# Interconnect_board_v1p9.net
KiCad netlist of a schematic drawn in EAGLE
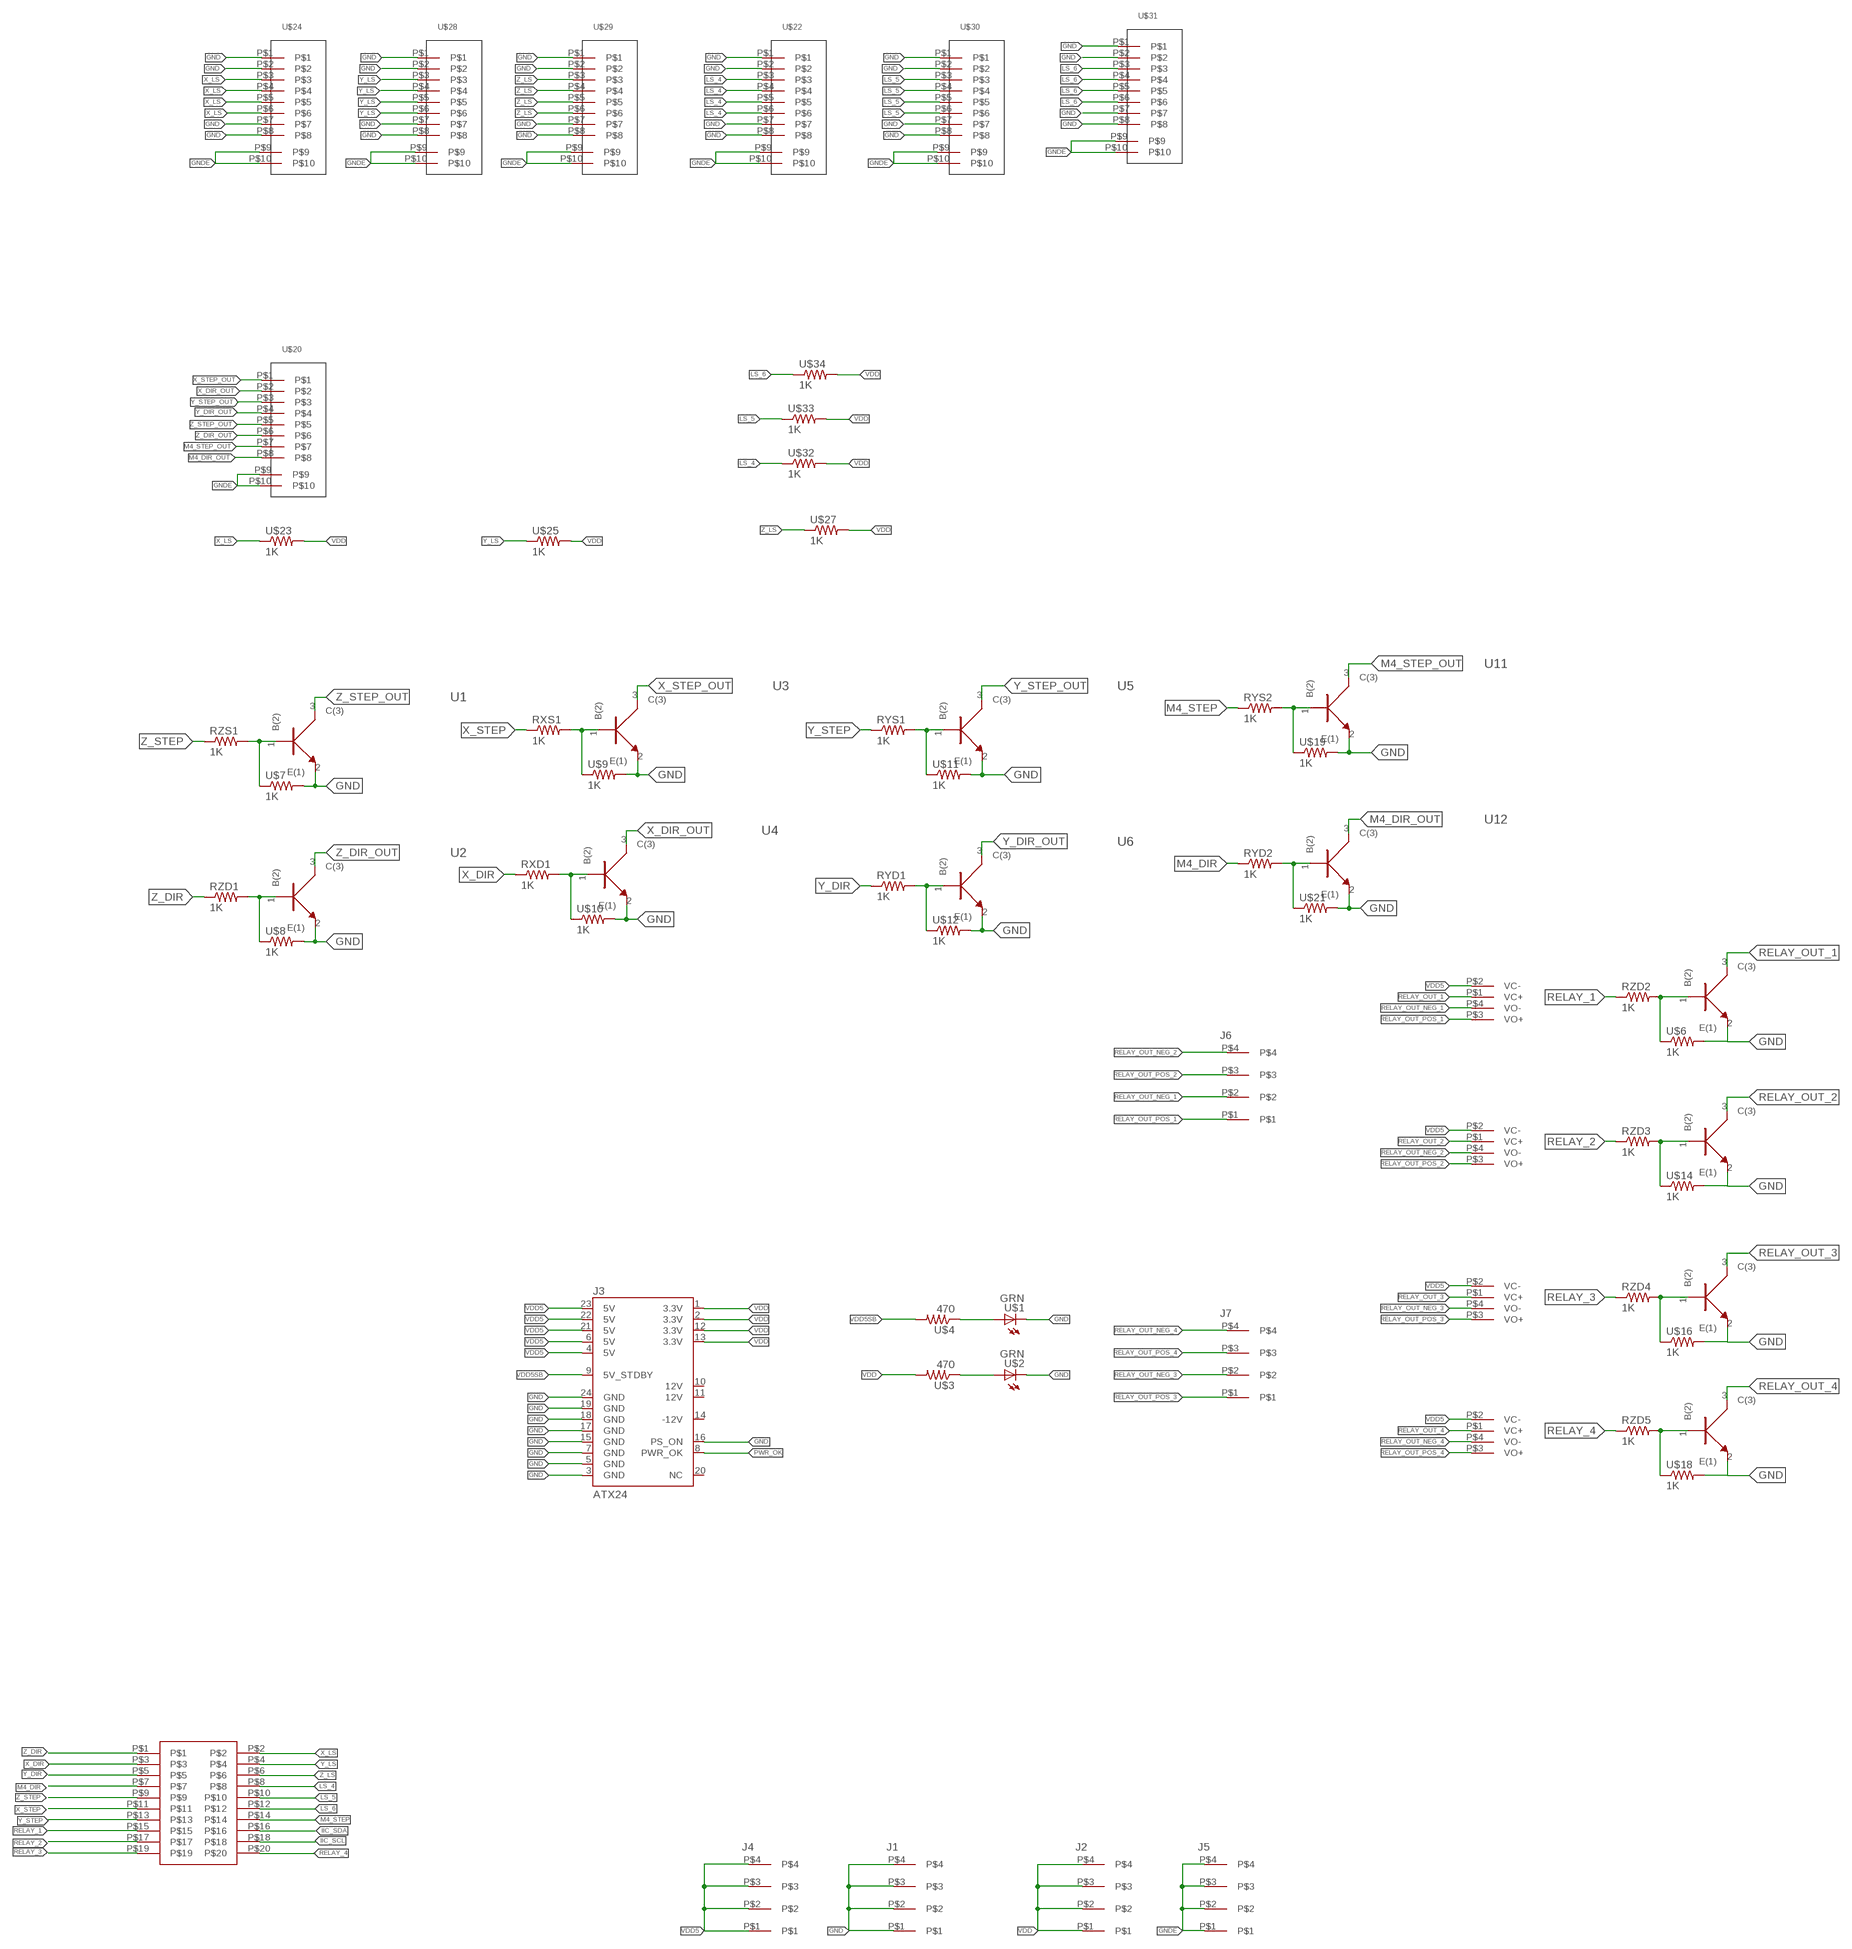
[diagram p0: schematic, sheet 1]

(export (version "E")
  (design (tool "Eeschema 10.0.6"))
  (components
    (comp (ref "J1")
      (value "3.81MM_1_X_4_RT_ANGLE_PLUG_HEADER")
      (footprint "eagle-import:1X4_3.81MM_PITCH")
      (libsource (lib "eagle-import") (part "3.81MM_1_X_4_RT_ANGLE_PLUG_HEADER"))
    )
    (comp (ref "J2")
      (value "3.81MM_1_X_4_RT_ANGLE_PLUG_HEADER")
      (footprint "eagle-import:1X4_3.81MM_PITCH")
      (libsource (lib "eagle-import") (part "3.81MM_1_X_4_RT_ANGLE_PLUG_HEADER"))
    )
    (comp (ref "J3")
      (value "ATX24")
      (footprint "eagle-import:ATX24_STRAIGHT")
      (libsource (lib "eagle-import") (part "ATX24"))
    )
    (comp (ref "J4")
      (value "3.81MM_1_X_4_RT_ANGLE_PLUG_HEADER")
      (footprint "eagle-import:1X4_3.81MM_PITCH")
      (libsource (lib "eagle-import") (part "3.81MM_1_X_4_RT_ANGLE_PLUG_HEADER"))
    )
    (comp (ref "J5")
      (value "3.81MM_1_X_4_RT_ANGLE_PLUG_HEADER")
      (footprint "eagle-import:1X4_3.81MM_PITCH")
      (libsource (lib "eagle-import") (part "3.81MM_1_X_4_RT_ANGLE_PLUG_HEADER"))
    )
    (comp (ref "J6")
      (value "3.81MM_1_X_4_RT_ANGLE_PLUG_HEADER")
      (footprint "eagle-import:1X4_3.81MM_PITCH")
      (libsource (lib "eagle-import") (part "3.81MM_1_X_4_RT_ANGLE_PLUG_HEADER"))
    )
    (comp (ref "J7")
      (value "3.81MM_1_X_4_RT_ANGLE_PLUG_HEADER")
      (footprint "eagle-import:1X4_3.81MM_PITCH")
      (libsource (lib "eagle-import") (part "3.81MM_1_X_4_RT_ANGLE_PLUG_HEADER"))
    )
    (comp (ref "RXD1")
      (value "R_0805_1K")
      (footprint "eagle-import:R_0805_1K")
      (libsource (lib "eagle-import") (part "R_0805_1K"))
    )
    (comp (ref "RXS1")
      (value "R_0805_1K")
      (footprint "eagle-import:R_0805_1K")
      (libsource (lib "eagle-import") (part "R_0805_1K"))
    )
    (comp (ref "RYD1")
      (value "R_0805_1K")
      (footprint "eagle-import:R_0805_1K")
      (libsource (lib "eagle-import") (part "R_0805_1K"))
    )
    (comp (ref "RYD2")
      (value "R_0805_1K")
      (footprint "eagle-import:R_0805_1K")
      (libsource (lib "eagle-import") (part "R_0805_1K"))
    )
    (comp (ref "RYS1")
      (value "R_0805_1K")
      (footprint "eagle-import:R_0805_1K")
      (libsource (lib "eagle-import") (part "R_0805_1K"))
    )
    (comp (ref "RYS2")
      (value "R_0805_1K")
      (footprint "eagle-import:R_0805_1K")
      (libsource (lib "eagle-import") (part "R_0805_1K"))
    )
    (comp (ref "RZD1")
      (value "R_0805_1K")
      (footprint "eagle-import:R_0805_1K")
      (libsource (lib "eagle-import") (part "R_0805_1K"))
    )
    (comp (ref "RZD2")
      (value "R_0805_1K")
      (footprint "eagle-import:R_0805_1K")
      (libsource (lib "eagle-import") (part "R_0805_1K"))
    )
    (comp (ref "RZD3")
      (value "R_0805_1K")
      (footprint "eagle-import:R_0805_1K")
      (libsource (lib "eagle-import") (part "R_0805_1K"))
    )
    (comp (ref "RZD4")
      (value "R_0805_1K")
      (footprint "eagle-import:R_0805_1K")
      (libsource (lib "eagle-import") (part "R_0805_1K"))
    )
    (comp (ref "RZD5")
      (value "R_0805_1K")
      (footprint "eagle-import:R_0805_1K")
      (libsource (lib "eagle-import") (part "R_0805_1K"))
    )
    (comp (ref "RZS1")
      (value "R_0805_1K")
      (footprint "eagle-import:R_0805_1K")
      (libsource (lib "eagle-import") (part "R_0805_1K"))
    )
    (comp (ref "U$1")
      (value "LED_0805_GREEN")
      (footprint "eagle-import:LED_0805_GREEN")
      (libsource (lib "eagle-import") (part "LED_0805_GREEN"))
    )
    (comp (ref "U$2")
      (value "LED_0805_GREEN")
      (footprint "eagle-import:LED_0805_GREEN")
      (libsource (lib "eagle-import") (part "LED_0805_GREEN"))
    )
    (comp (ref "U$3")
      (value "R_0805_470")
      (footprint "eagle-import:R_0805_470")
      (libsource (lib "eagle-import") (part "R_0805_470"))
    )
    (comp (ref "U$4")
      (value "R_0805_470")
      (footprint "eagle-import:R_0805_470")
      (libsource (lib "eagle-import") (part "R_0805_470"))
    )
    (comp (ref "U$5")
      (value "RELAY_KYOTO_KF0604D")
      (footprint "eagle-import:RELAY_KYOTO_KF0604D")
      (libsource (lib "eagle-import") (part "RELAY_KYOTO_KF0604D"))
    )
    (comp (ref "U$6")
      (value "R_0805_1K")
      (footprint "eagle-import:R_0805_1K")
      (libsource (lib "eagle-import") (part "R_0805_1K"))
    )
    (comp (ref "U$7")
      (value "R_0805_1K")
      (footprint "eagle-import:R_0805_1K")
      (libsource (lib "eagle-import") (part "R_0805_1K"))
    )
    (comp (ref "U$8")
      (value "R_0805_1K")
      (footprint "eagle-import:R_0805_1K")
      (libsource (lib "eagle-import") (part "R_0805_1K"))
    )
    (comp (ref "U$9")
      (value "R_0805_1K")
      (footprint "eagle-import:R_0805_1K")
      (libsource (lib "eagle-import") (part "R_0805_1K"))
    )
    (comp (ref "U$10")
      (value "R_0805_1K")
      (footprint "eagle-import:R_0805_1K")
      (libsource (lib "eagle-import") (part "R_0805_1K"))
    )
    (comp (ref "U$11")
      (value "R_0805_1K")
      (footprint "eagle-import:R_0805_1K")
      (libsource (lib "eagle-import") (part "R_0805_1K"))
    )
    (comp (ref "U$12")
      (value "R_0805_1K")
      (footprint "eagle-import:R_0805_1K")
      (libsource (lib "eagle-import") (part "R_0805_1K"))
    )
    (comp (ref "U$13")
      (value "RELAY_KYOTO_KF0604D")
      (footprint "eagle-import:RELAY_KYOTO_KF0604D")
      (libsource (lib "eagle-import") (part "RELAY_KYOTO_KF0604D"))
    )
    (comp (ref "U$14")
      (value "R_0805_1K")
      (footprint "eagle-import:R_0805_1K")
      (libsource (lib "eagle-import") (part "R_0805_1K"))
    )
    (comp (ref "U$15")
      (value "RELAY_KYOTO_KF0604D")
      (footprint "eagle-import:RELAY_KYOTO_KF0604D")
      (libsource (lib "eagle-import") (part "RELAY_KYOTO_KF0604D"))
    )
    (comp (ref "U$16")
      (value "R_0805_1K")
      (footprint "eagle-import:R_0805_1K")
      (libsource (lib "eagle-import") (part "R_0805_1K"))
    )
    (comp (ref "U$17")
      (value "RELAY_KYOTO_KF0604D")
      (footprint "eagle-import:RELAY_KYOTO_KF0604D")
      (libsource (lib "eagle-import") (part "RELAY_KYOTO_KF0604D"))
    )
    (comp (ref "U$18")
      (value "R_0805_1K")
      (footprint "eagle-import:R_0805_1K")
      (libsource (lib "eagle-import") (part "R_0805_1K"))
    )
    (comp (ref "U$19")
      (value "R_0805_1K")
      (footprint "eagle-import:R_0805_1K")
      (libsource (lib "eagle-import") (part "R_0805_1K"))
    )
    (comp (ref "U$20")
      (value "RJ45_SMTRJ")
      (footprint "eagle-import:RJ45_SMT")
      (libsource (lib "eagle-import") (part "RJ45_SMTRJ"))
    )
    (comp (ref "U$21")
      (value "R_0805_1K")
      (footprint "eagle-import:R_0805_1K")
      (libsource (lib "eagle-import") (part "R_0805_1K"))
    )
    (comp (ref "U$22")
      (value "RJ45_SMTRJ")
      (footprint "eagle-import:RJ45_SMT")
      (libsource (lib "eagle-import") (part "RJ45_SMTRJ"))
    )
    (comp (ref "U$23")
      (value "R_0805_1K")
      (footprint "eagle-import:R_0805_1K")
      (libsource (lib "eagle-import") (part "R_0805_1K"))
    )
    (comp (ref "U$24")
      (value "RJ45_SMTRJ")
      (footprint "eagle-import:RJ45_SMT")
      (libsource (lib "eagle-import") (part "RJ45_SMTRJ"))
    )
    (comp (ref "U$25")
      (value "R_0805_1K")
      (footprint "eagle-import:R_0805_1K")
      (libsource (lib "eagle-import") (part "R_0805_1K"))
    )
    (comp (ref "U$26")
      (value "2_X_10_HEADER_GENERIC")
      (footprint "eagle-import:2_X_10_.1_INCH")
      (libsource (lib "eagle-import") (part "2_X_10_HEADER_GENERIC"))
    )
    (comp (ref "U$27")
      (value "R_0805_1K")
      (footprint "eagle-import:R_0805_1K")
      (libsource (lib "eagle-import") (part "R_0805_1K"))
    )
    (comp (ref "U$28")
      (value "RJ45_SMTRJ")
      (footprint "eagle-import:RJ45_SMT")
      (libsource (lib "eagle-import") (part "RJ45_SMTRJ"))
    )
    (comp (ref "U$29")
      (value "RJ45_SMTRJ")
      (footprint "eagle-import:RJ45_SMT")
      (libsource (lib "eagle-import") (part "RJ45_SMTRJ"))
    )
    (comp (ref "U$30")
      (value "RJ45_SMTRJ")
      (footprint "eagle-import:RJ45_SMT")
      (libsource (lib "eagle-import") (part "RJ45_SMTRJ"))
    )
    (comp (ref "U$31")
      (value "RJ45_SMTRJ")
      (footprint "eagle-import:RJ45_SMT")
      (libsource (lib "eagle-import") (part "RJ45_SMTRJ"))
    )
    (comp (ref "U$32")
      (value "R_0805_1K")
      (footprint "eagle-import:R_0805_1K")
      (libsource (lib "eagle-import") (part "R_0805_1K"))
    )
    (comp (ref "U$33")
      (value "R_0805_1K")
      (footprint "eagle-import:R_0805_1K")
      (libsource (lib "eagle-import") (part "R_0805_1K"))
    )
    (comp (ref "U$34")
      (value "R_0805_1K")
      (footprint "eagle-import:R_0805_1K")
      (libsource (lib "eagle-import") (part "R_0805_1K"))
    )
    (comp (ref "U1")
      (value "BC846BW")
      (footprint "eagle-import:SOT323")
      (libsource (lib "eagle-import") (part "BC846BW"))
    )
    (comp (ref "U2")
      (value "BC846BW")
      (footprint "eagle-import:SOT323")
      (libsource (lib "eagle-import") (part "BC846BW"))
    )
    (comp (ref "U3")
      (value "BC846BW")
      (footprint "eagle-import:SOT323")
      (libsource (lib "eagle-import") (part "BC846BW"))
    )
    (comp (ref "U4")
      (value "BC846BW")
      (footprint "eagle-import:SOT323")
      (libsource (lib "eagle-import") (part "BC846BW"))
    )
    (comp (ref "U5")
      (value "BC846BW")
      (footprint "eagle-import:SOT323")
      (libsource (lib "eagle-import") (part "BC846BW"))
    )
    (comp (ref "U6")
      (value "BC846BW")
      (footprint "eagle-import:SOT323")
      (libsource (lib "eagle-import") (part "BC846BW"))
    )
    (comp (ref "U7")
      (value "BC846BW")
      (footprint "eagle-import:SOT323")
      (libsource (lib "eagle-import") (part "BC846BW"))
    )
    (comp (ref "U8")
      (value "BC846BW")
      (footprint "eagle-import:SOT323")
      (libsource (lib "eagle-import") (part "BC846BW"))
    )
    (comp (ref "U9")
      (value "BC846BW")
      (footprint "eagle-import:SOT323")
      (libsource (lib "eagle-import") (part "BC846BW"))
    )
    (comp (ref "U10")
      (value "BC846BW")
      (footprint "eagle-import:SOT323")
      (libsource (lib "eagle-import") (part "BC846BW"))
    )
    (comp (ref "U11")
      (value "BC846BW")
      (footprint "eagle-import:SOT323")
      (libsource (lib "eagle-import") (part "BC846BW"))
    )
    (comp (ref "U12")
      (value "BC846BW")
      (footprint "eagle-import:SOT323")
      (libsource (lib "eagle-import") (part "BC846BW"))
    )
  )
  (nets
    (net (code "1") (name "GND") (class "Default")
      (node (ref "J1") (pin "P$1") (pinfunction "P$1_P$1") (pintype "bidirectional"))
      (node (ref "J1") (pin "P$2") (pinfunction "P$2_P$2") (pintype "bidirectional"))
      (node (ref "J1") (pin "P$3") (pinfunction "P$3_P$3") (pintype "bidirectional"))
      (node (ref "J1") (pin "P$4") (pinfunction "P$4_P$4") (pintype "bidirectional"))
      (node (ref "J3") (pin "15") (pinfunction "GND_15") (pintype "bidirectional"))
      (node (ref "J3") (pin "16") (pinfunction "PS_ON_16") (pintype "bidirectional"))
      (node (ref "J3") (pin "17") (pinfunction "GND_17") (pintype "bidirectional"))
      (node (ref "J3") (pin "18") (pinfunction "GND_18") (pintype "bidirectional"))
      (node (ref "J3") (pin "19") (pinfunction "GND_19") (pintype "bidirectional"))
      (node (ref "J3") (pin "24") (pinfunction "GND_24") (pintype "bidirectional"))
      (node (ref "J3") (pin "3") (pinfunction "GND_3") (pintype "bidirectional"))
      (node (ref "J3") (pin "5") (pinfunction "GND_5") (pintype "bidirectional"))
      (node (ref "J3") (pin "7") (pinfunction "GND_7") (pintype "bidirectional"))
      (node (ref "U$1") (pin "C") (pinfunction "C_C") (pintype "passive"))
      (node (ref "U$10") (pin "2") (pinfunction "2_2") (pintype "passive"))
      (node (ref "U$11") (pin "2") (pinfunction "2_2") (pintype "passive"))
      (node (ref "U$12") (pin "2") (pinfunction "2_2") (pintype "passive"))
      (node (ref "U$14") (pin "2") (pinfunction "2_2") (pintype "passive"))
      (node (ref "U$16") (pin "2") (pinfunction "2_2") (pintype "passive"))
      (node (ref "U$18") (pin "2") (pinfunction "2_2") (pintype "passive"))
      (node (ref "U$19") (pin "2") (pinfunction "2_2") (pintype "passive"))
      (node (ref "U$2") (pin "C") (pinfunction "C_C") (pintype "passive"))
      (node (ref "U$21") (pin "2") (pinfunction "2_2") (pintype "passive"))
      (node (ref "U$22") (pin "P$1") (pinfunction "P$1_P$1") (pintype "bidirectional"))
      (node (ref "U$22") (pin "P$2") (pinfunction "P$2_P$2") (pintype "bidirectional"))
      (node (ref "U$22") (pin "P$7") (pinfunction "P$7_P$7") (pintype "bidirectional"))
      (node (ref "U$22") (pin "P$8") (pinfunction "P$8_P$8") (pintype "bidirectional"))
      (node (ref "U$24") (pin "P$1") (pinfunction "P$1_P$1") (pintype "bidirectional"))
      (node (ref "U$24") (pin "P$2") (pinfunction "P$2_P$2") (pintype "bidirectional"))
      (node (ref "U$24") (pin "P$7") (pinfunction "P$7_P$7") (pintype "bidirectional"))
      (node (ref "U$24") (pin "P$8") (pinfunction "P$8_P$8") (pintype "bidirectional"))
      (node (ref "U$28") (pin "P$1") (pinfunction "P$1_P$1") (pintype "bidirectional"))
      (node (ref "U$28") (pin "P$2") (pinfunction "P$2_P$2") (pintype "bidirectional"))
      (node (ref "U$28") (pin "P$7") (pinfunction "P$7_P$7") (pintype "bidirectional"))
      (node (ref "U$28") (pin "P$8") (pinfunction "P$8_P$8") (pintype "bidirectional"))
      (node (ref "U$29") (pin "P$1") (pinfunction "P$1_P$1") (pintype "bidirectional"))
      (node (ref "U$29") (pin "P$2") (pinfunction "P$2_P$2") (pintype "bidirectional"))
      (node (ref "U$29") (pin "P$7") (pinfunction "P$7_P$7") (pintype "bidirectional"))
      (node (ref "U$29") (pin "P$8") (pinfunction "P$8_P$8") (pintype "bidirectional"))
      (node (ref "U$30") (pin "P$1") (pinfunction "P$1_P$1") (pintype "bidirectional"))
      (node (ref "U$30") (pin "P$2") (pinfunction "P$2_P$2") (pintype "bidirectional"))
      (node (ref "U$30") (pin "P$7") (pinfunction "P$7_P$7") (pintype "bidirectional"))
      (node (ref "U$30") (pin "P$8") (pinfunction "P$8_P$8") (pintype "bidirectional"))
      (node (ref "U$31") (pin "P$1") (pinfunction "P$1_P$1") (pintype "bidirectional"))
      (node (ref "U$31") (pin "P$2") (pinfunction "P$2_P$2") (pintype "bidirectional"))
      (node (ref "U$31") (pin "P$7") (pinfunction "P$7_P$7") (pintype "bidirectional"))
      (node (ref "U$31") (pin "P$8") (pinfunction "P$8_P$8") (pintype "bidirectional"))
      (node (ref "U$6") (pin "2") (pinfunction "2_2") (pintype "passive"))
      (node (ref "U$7") (pin "2") (pinfunction "2_2") (pintype "passive"))
      (node (ref "U$8") (pin "2") (pinfunction "2_2") (pintype "passive"))
      (node (ref "U$9") (pin "2") (pinfunction "2_2") (pintype "passive"))
      (node (ref "U1") (pin "2") (pinfunction "E(1)_2") (pintype "output"))
      (node (ref "U10") (pin "2") (pinfunction "E(1)_2") (pintype "output"))
      (node (ref "U11") (pin "2") (pinfunction "E(1)_2") (pintype "output"))
      (node (ref "U12") (pin "2") (pinfunction "E(1)_2") (pintype "output"))
      (node (ref "U2") (pin "2") (pinfunction "E(1)_2") (pintype "output"))
      (node (ref "U3") (pin "2") (pinfunction "E(1)_2") (pintype "output"))
      (node (ref "U4") (pin "2") (pinfunction "E(1)_2") (pintype "output"))
      (node (ref "U5") (pin "2") (pinfunction "E(1)_2") (pintype "output"))
      (node (ref "U6") (pin "2") (pinfunction "E(1)_2") (pintype "output"))
      (node (ref "U7") (pin "2") (pinfunction "E(1)_2") (pintype "output"))
      (node (ref "U8") (pin "2") (pinfunction "E(1)_2") (pintype "output"))
      (node (ref "U9") (pin "2") (pinfunction "E(1)_2") (pintype "output"))
    )
    (net (code "2") (name "GNDE") (class "Default")
      (node (ref "J5") (pin "P$1") (pinfunction "P$1_P$1") (pintype "bidirectional"))
      (node (ref "J5") (pin "P$2") (pinfunction "P$2_P$2") (pintype "bidirectional"))
      (node (ref "J5") (pin "P$3") (pinfunction "P$3_P$3") (pintype "bidirectional"))
      (node (ref "J5") (pin "P$4") (pinfunction "P$4_P$4") (pintype "bidirectional"))
      (node (ref "U$20") (pin "P$10") (pinfunction "P$10_P$10") (pintype "bidirectional"))
      (node (ref "U$20") (pin "P$9") (pinfunction "P$9_P$9") (pintype "bidirectional"))
      (node (ref "U$22") (pin "P$10") (pinfunction "P$10_P$10") (pintype "bidirectional"))
      (node (ref "U$22") (pin "P$9") (pinfunction "P$9_P$9") (pintype "bidirectional"))
      (node (ref "U$24") (pin "P$10") (pinfunction "P$10_P$10") (pintype "bidirectional"))
      (node (ref "U$24") (pin "P$9") (pinfunction "P$9_P$9") (pintype "bidirectional"))
      (node (ref "U$28") (pin "P$10") (pinfunction "P$10_P$10") (pintype "bidirectional"))
      (node (ref "U$28") (pin "P$9") (pinfunction "P$9_P$9") (pintype "bidirectional"))
      (node (ref "U$29") (pin "P$10") (pinfunction "P$10_P$10") (pintype "bidirectional"))
      (node (ref "U$29") (pin "P$9") (pinfunction "P$9_P$9") (pintype "bidirectional"))
      (node (ref "U$30") (pin "P$10") (pinfunction "P$10_P$10") (pintype "bidirectional"))
      (node (ref "U$30") (pin "P$9") (pinfunction "P$9_P$9") (pintype "bidirectional"))
      (node (ref "U$31") (pin "P$10") (pinfunction "P$10_P$10") (pintype "bidirectional"))
      (node (ref "U$31") (pin "P$9") (pinfunction "P$9_P$9") (pintype "bidirectional"))
    )
    (net (code "3") (name "IIC_SCL") (class "Default")
      (node (ref "U$26") (pin "P$18") (pinfunction "P$18_P$18") (pintype "bidirectional"))
    )
    (net (code "4") (name "IIC_SDA") (class "Default")
      (node (ref "U$26") (pin "P$16") (pinfunction "P$16_P$16") (pintype "bidirectional"))
    )
    (net (code "5") (name "LS_4") (class "Default")
      (node (ref "U$22") (pin "P$3") (pinfunction "P$3_P$3") (pintype "bidirectional"))
      (node (ref "U$22") (pin "P$4") (pinfunction "P$4_P$4") (pintype "bidirectional"))
      (node (ref "U$22") (pin "P$5") (pinfunction "P$5_P$5") (pintype "bidirectional"))
      (node (ref "U$22") (pin "P$6") (pinfunction "P$6_P$6") (pintype "bidirectional"))
      (node (ref "U$26") (pin "P$8") (pinfunction "P$8_P$8") (pintype "bidirectional"))
      (node (ref "U$32") (pin "1") (pinfunction "1_1") (pintype "passive"))
    )
    (net (code "6") (name "LS_5") (class "Default")
      (node (ref "U$26") (pin "P$10") (pinfunction "P$10_P$10") (pintype "bidirectional"))
      (node (ref "U$30") (pin "P$3") (pinfunction "P$3_P$3") (pintype "bidirectional"))
      (node (ref "U$30") (pin "P$4") (pinfunction "P$4_P$4") (pintype "bidirectional"))
      (node (ref "U$30") (pin "P$5") (pinfunction "P$5_P$5") (pintype "bidirectional"))
      (node (ref "U$30") (pin "P$6") (pinfunction "P$6_P$6") (pintype "bidirectional"))
      (node (ref "U$33") (pin "1") (pinfunction "1_1") (pintype "passive"))
    )
    (net (code "7") (name "LS_6") (class "Default")
      (node (ref "U$26") (pin "P$12") (pinfunction "P$12_P$12") (pintype "bidirectional"))
      (node (ref "U$31") (pin "P$3") (pinfunction "P$3_P$3") (pintype "bidirectional"))
      (node (ref "U$31") (pin "P$4") (pinfunction "P$4_P$4") (pintype "bidirectional"))
      (node (ref "U$31") (pin "P$5") (pinfunction "P$5_P$5") (pintype "bidirectional"))
      (node (ref "U$31") (pin "P$6") (pinfunction "P$6_P$6") (pintype "bidirectional"))
      (node (ref "U$34") (pin "1") (pinfunction "1_1") (pintype "passive"))
    )
    (net (code "8") (name "M4_DIR") (class "Default")
      (node (ref "RYD2") (pin "1") (pinfunction "1_1") (pintype "passive"))
      (node (ref "U$26") (pin "P$7") (pinfunction "P$7_P$7") (pintype "bidirectional"))
    )
    (net (code "9") (name "M4_DIR_OUT") (class "Default")
      (node (ref "U$20") (pin "P$8") (pinfunction "P$8_P$8") (pintype "bidirectional"))
      (node (ref "U12") (pin "3") (pinfunction "C(3)_3") (pintype "input"))
    )
    (net (code "10") (name "M4_STEP") (class "Default")
      (node (ref "RYS2") (pin "1") (pinfunction "1_1") (pintype "passive"))
      (node (ref "U$26") (pin "P$14") (pinfunction "P$14_P$14") (pintype "bidirectional"))
    )
    (net (code "11") (name "M4_STEP_OUT") (class "Default")
      (node (ref "U$20") (pin "P$7") (pinfunction "P$7_P$7") (pintype "bidirectional"))
      (node (ref "U11") (pin "3") (pinfunction "C(3)_3") (pintype "input"))
    )
    (net (code "12") (name "Net-(U$1-PadA)") (class "Default")
      (node (ref "U$1") (pin "A") (pinfunction "A_A") (pintype "passive"))
      (node (ref "U$4") (pin "1") (pinfunction "1_1") (pintype "passive"))
    )
    (net (code "13") (name "Net-(U$2-PadA)") (class "Default")
      (node (ref "U$2") (pin "A") (pinfunction "A_A") (pintype "passive"))
      (node (ref "U$3") (pin "1") (pinfunction "1_1") (pintype "passive"))
    )
    (net (code "14") (name "Net-(U1-B(2))") (class "Default")
      (node (ref "RZS1") (pin "2") (pinfunction "2_2") (pintype "passive"))
      (node (ref "U$7") (pin "1") (pinfunction "1_1") (pintype "passive"))
      (node (ref "U1") (pin "1") (pinfunction "B(2)_1") (pintype "input"))
    )
    (net (code "15") (name "Net-(U2-B(2))") (class "Default")
      (node (ref "RZD1") (pin "2") (pinfunction "2_2") (pintype "passive"))
      (node (ref "U$8") (pin "1") (pinfunction "1_1") (pintype "passive"))
      (node (ref "U2") (pin "1") (pinfunction "B(2)_1") (pintype "input"))
    )
    (net (code "16") (name "Net-(U3-B(2))") (class "Default")
      (node (ref "RXS1") (pin "2") (pinfunction "2_2") (pintype "passive"))
      (node (ref "U$9") (pin "1") (pinfunction "1_1") (pintype "passive"))
      (node (ref "U3") (pin "1") (pinfunction "B(2)_1") (pintype "input"))
    )
    (net (code "17") (name "Net-(U4-B(2))") (class "Default")
      (node (ref "RXD1") (pin "2") (pinfunction "2_2") (pintype "passive"))
      (node (ref "U$10") (pin "1") (pinfunction "1_1") (pintype "passive"))
      (node (ref "U4") (pin "1") (pinfunction "B(2)_1") (pintype "input"))
    )
    (net (code "18") (name "Net-(U5-B(2))") (class "Default")
      (node (ref "RYS1") (pin "2") (pinfunction "2_2") (pintype "passive"))
      (node (ref "U$11") (pin "1") (pinfunction "1_1") (pintype "passive"))
      (node (ref "U5") (pin "1") (pinfunction "B(2)_1") (pintype "input"))
    )
    (net (code "19") (name "Net-(U6-B(2))") (class "Default")
      (node (ref "RYD1") (pin "2") (pinfunction "2_2") (pintype "passive"))
      (node (ref "U$12") (pin "1") (pinfunction "1_1") (pintype "passive"))
      (node (ref "U6") (pin "1") (pinfunction "B(2)_1") (pintype "input"))
    )
    (net (code "20") (name "Net-(U7-B(2))") (class "Default")
      (node (ref "RZD2") (pin "2") (pinfunction "2_2") (pintype "passive"))
      (node (ref "U$6") (pin "1") (pinfunction "1_1") (pintype "passive"))
      (node (ref "U7") (pin "1") (pinfunction "B(2)_1") (pintype "input"))
    )
    (net (code "21") (name "Net-(U8-B(2))") (class "Default")
      (node (ref "RZD3") (pin "2") (pinfunction "2_2") (pintype "passive"))
      (node (ref "U$14") (pin "1") (pinfunction "1_1") (pintype "passive"))
      (node (ref "U8") (pin "1") (pinfunction "B(2)_1") (pintype "input"))
    )
    (net (code "22") (name "Net-(U9-B(2))") (class "Default")
      (node (ref "RZD4") (pin "2") (pinfunction "2_2") (pintype "passive"))
      (node (ref "U$16") (pin "1") (pinfunction "1_1") (pintype "passive"))
      (node (ref "U9") (pin "1") (pinfunction "B(2)_1") (pintype "input"))
    )
    (net (code "23") (name "Net-(U10-B(2))") (class "Default")
      (node (ref "RZD5") (pin "2") (pinfunction "2_2") (pintype "passive"))
      (node (ref "U$18") (pin "1") (pinfunction "1_1") (pintype "passive"))
      (node (ref "U10") (pin "1") (pinfunction "B(2)_1") (pintype "input"))
    )
    (net (code "24") (name "Net-(U11-B(2))") (class "Default")
      (node (ref "RYS2") (pin "2") (pinfunction "2_2") (pintype "passive"))
      (node (ref "U$19") (pin "1") (pinfunction "1_1") (pintype "passive"))
      (node (ref "U11") (pin "1") (pinfunction "B(2)_1") (pintype "input"))
    )
    (net (code "25") (name "Net-(U12-B(2))") (class "Default")
      (node (ref "RYD2") (pin "2") (pinfunction "2_2") (pintype "passive"))
      (node (ref "U$21") (pin "1") (pinfunction "1_1") (pintype "passive"))
      (node (ref "U12") (pin "1") (pinfunction "B(2)_1") (pintype "input"))
    )
    (net (code "26") (name "PWR_OK") (class "Default")
      (node (ref "J3") (pin "8") (pinfunction "PWR_OK_8") (pintype "bidirectional"))
    )
    (net (code "27") (name "RELAY_1") (class "Default")
      (node (ref "RZD2") (pin "1") (pinfunction "1_1") (pintype "passive"))
      (node (ref "U$26") (pin "P$15") (pinfunction "P$15_P$15") (pintype "bidirectional"))
    )
    (net (code "28") (name "RELAY_2") (class "Default")
      (node (ref "RZD3") (pin "1") (pinfunction "1_1") (pintype "passive"))
      (node (ref "U$26") (pin "P$17") (pinfunction "P$17_P$17") (pintype "bidirectional"))
    )
    (net (code "29") (name "RELAY_3") (class "Default")
      (node (ref "RZD4") (pin "1") (pinfunction "1_1") (pintype "passive"))
      (node (ref "U$26") (pin "P$19") (pinfunction "P$19_P$19") (pintype "bidirectional"))
    )
    (net (code "30") (name "RELAY_4") (class "Default")
      (node (ref "RZD5") (pin "1") (pinfunction "1_1") (pintype "passive"))
      (node (ref "U$26") (pin "P$20") (pinfunction "P$20_P$20") (pintype "bidirectional"))
    )
    (net (code "31") (name "RELAY_OUT_1") (class "Default")
      (node (ref "U$5") (pin "P$1") (pinfunction "VC+_P$1") (pintype "bidirectional"))
      (node (ref "U7") (pin "3") (pinfunction "C(3)_3") (pintype "input"))
    )
    (net (code "32") (name "RELAY_OUT_2") (class "Default")
      (node (ref "U$13") (pin "P$1") (pinfunction "VC+_P$1") (pintype "bidirectional"))
      (node (ref "U8") (pin "3") (pinfunction "C(3)_3") (pintype "input"))
    )
    (net (code "33") (name "RELAY_OUT_3") (class "Default")
      (node (ref "U$15") (pin "P$1") (pinfunction "VC+_P$1") (pintype "bidirectional"))
      (node (ref "U9") (pin "3") (pinfunction "C(3)_3") (pintype "input"))
    )
    (net (code "34") (name "RELAY_OUT_4") (class "Default")
      (node (ref "U$17") (pin "P$1") (pinfunction "VC+_P$1") (pintype "bidirectional"))
      (node (ref "U10") (pin "3") (pinfunction "C(3)_3") (pintype "input"))
    )
    (net (code "35") (name "RELAY_OUT_NEG_1") (class "Default")
      (node (ref "J6") (pin "P$2") (pinfunction "P$2_P$2") (pintype "bidirectional"))
      (node (ref "U$5") (pin "P$4") (pinfunction "VO-_P$4") (pintype "bidirectional"))
    )
    (net (code "36") (name "RELAY_OUT_NEG_2") (class "Default")
      (node (ref "J6") (pin "P$4") (pinfunction "P$4_P$4") (pintype "bidirectional"))
      (node (ref "U$13") (pin "P$4") (pinfunction "VO-_P$4") (pintype "bidirectional"))
    )
    (net (code "37") (name "RELAY_OUT_NEG_3") (class "Default")
      (node (ref "J7") (pin "P$2") (pinfunction "P$2_P$2") (pintype "bidirectional"))
      (node (ref "U$15") (pin "P$4") (pinfunction "VO-_P$4") (pintype "bidirectional"))
    )
    (net (code "38") (name "RELAY_OUT_NEG_4") (class "Default")
      (node (ref "J7") (pin "P$4") (pinfunction "P$4_P$4") (pintype "bidirectional"))
      (node (ref "U$17") (pin "P$4") (pinfunction "VO-_P$4") (pintype "bidirectional"))
    )
    (net (code "39") (name "RELAY_OUT_POS_1") (class "Default")
      (node (ref "J6") (pin "P$1") (pinfunction "P$1_P$1") (pintype "bidirectional"))
      (node (ref "U$5") (pin "P$3") (pinfunction "VO+_P$3") (pintype "bidirectional"))
    )
    (net (code "40") (name "RELAY_OUT_POS_2") (class "Default")
      (node (ref "J6") (pin "P$3") (pinfunction "P$3_P$3") (pintype "bidirectional"))
      (node (ref "U$13") (pin "P$3") (pinfunction "VO+_P$3") (pintype "bidirectional"))
    )
    (net (code "41") (name "RELAY_OUT_POS_3") (class "Default")
      (node (ref "J7") (pin "P$1") (pinfunction "P$1_P$1") (pintype "bidirectional"))
      (node (ref "U$15") (pin "P$3") (pinfunction "VO+_P$3") (pintype "bidirectional"))
    )
    (net (code "42") (name "RELAY_OUT_POS_4") (class "Default")
      (node (ref "J7") (pin "P$3") (pinfunction "P$3_P$3") (pintype "bidirectional"))
      (node (ref "U$17") (pin "P$3") (pinfunction "VO+_P$3") (pintype "bidirectional"))
    )
    (net (code "43") (name "VDD") (class "Default")
      (node (ref "J2") (pin "P$1") (pinfunction "P$1_P$1") (pintype "bidirectional"))
      (node (ref "J2") (pin "P$2") (pinfunction "P$2_P$2") (pintype "bidirectional"))
      (node (ref "J2") (pin "P$3") (pinfunction "P$3_P$3") (pintype "bidirectional"))
      (node (ref "J2") (pin "P$4") (pinfunction "P$4_P$4") (pintype "bidirectional"))
      (node (ref "J3") (pin "1") (pinfunction "3.3V_1") (pintype "bidirectional"))
      (node (ref "J3") (pin "12") (pinfunction "3.3V_12") (pintype "bidirectional"))
      (node (ref "J3") (pin "13") (pinfunction "3.3V_13") (pintype "bidirectional"))
      (node (ref "J3") (pin "2") (pinfunction "3.3V_2") (pintype "bidirectional"))
      (node (ref "U$23") (pin "2") (pinfunction "2_2") (pintype "passive"))
      (node (ref "U$25") (pin "2") (pinfunction "2_2") (pintype "passive"))
      (node (ref "U$27") (pin "2") (pinfunction "2_2") (pintype "passive"))
      (node (ref "U$3") (pin "2") (pinfunction "2_2") (pintype "passive"))
      (node (ref "U$32") (pin "2") (pinfunction "2_2") (pintype "passive"))
      (node (ref "U$33") (pin "2") (pinfunction "2_2") (pintype "passive"))
      (node (ref "U$34") (pin "2") (pinfunction "2_2") (pintype "passive"))
    )
    (net (code "44") (name "VDD5") (class "Default")
      (node (ref "J3") (pin "21") (pinfunction "5V_21") (pintype "bidirectional"))
      (node (ref "J3") (pin "22") (pinfunction "5V_22") (pintype "bidirectional"))
      (node (ref "J3") (pin "23") (pinfunction "5V_23") (pintype "bidirectional"))
      (node (ref "J3") (pin "4") (pinfunction "5V_4") (pintype "bidirectional"))
      (node (ref "J3") (pin "6") (pinfunction "5V_6") (pintype "bidirectional"))
      (node (ref "J4") (pin "P$1") (pinfunction "P$1_P$1") (pintype "bidirectional"))
      (node (ref "J4") (pin "P$2") (pinfunction "P$2_P$2") (pintype "bidirectional"))
      (node (ref "J4") (pin "P$3") (pinfunction "P$3_P$3") (pintype "bidirectional"))
      (node (ref "J4") (pin "P$4") (pinfunction "P$4_P$4") (pintype "bidirectional"))
      (node (ref "U$13") (pin "P$2") (pinfunction "VC-_P$2") (pintype "bidirectional"))
      (node (ref "U$15") (pin "P$2") (pinfunction "VC-_P$2") (pintype "bidirectional"))
      (node (ref "U$17") (pin "P$2") (pinfunction "VC-_P$2") (pintype "bidirectional"))
      (node (ref "U$5") (pin "P$2") (pinfunction "VC-_P$2") (pintype "bidirectional"))
    )
    (net (code "45") (name "VDD5SB") (class "Default")
      (node (ref "J3") (pin "9") (pinfunction "5V_STDBY_9") (pintype "bidirectional"))
      (node (ref "U$4") (pin "2") (pinfunction "2_2") (pintype "passive"))
    )
    (net (code "46") (name "X_DIR") (class "Default")
      (node (ref "RXD1") (pin "1") (pinfunction "1_1") (pintype "passive"))
      (node (ref "U$26") (pin "P$3") (pinfunction "P$3_P$3") (pintype "bidirectional"))
    )
    (net (code "47") (name "X_DIR_OUT") (class "Default")
      (node (ref "U$20") (pin "P$2") (pinfunction "P$2_P$2") (pintype "bidirectional"))
      (node (ref "U4") (pin "3") (pinfunction "C(3)_3") (pintype "input"))
    )
    (net (code "48") (name "X_LS") (class "Default")
      (node (ref "U$23") (pin "1") (pinfunction "1_1") (pintype "passive"))
      (node (ref "U$24") (pin "P$3") (pinfunction "P$3_P$3") (pintype "bidirectional"))
      (node (ref "U$24") (pin "P$4") (pinfunction "P$4_P$4") (pintype "bidirectional"))
      (node (ref "U$24") (pin "P$5") (pinfunction "P$5_P$5") (pintype "bidirectional"))
      (node (ref "U$24") (pin "P$6") (pinfunction "P$6_P$6") (pintype "bidirectional"))
      (node (ref "U$26") (pin "P$2") (pinfunction "P$2_P$2") (pintype "bidirectional"))
    )
    (net (code "49") (name "X_STEP") (class "Default")
      (node (ref "RXS1") (pin "1") (pinfunction "1_1") (pintype "passive"))
      (node (ref "U$26") (pin "P$11") (pinfunction "P$11_P$11") (pintype "bidirectional"))
    )
    (net (code "50") (name "X_STEP_OUT") (class "Default")
      (node (ref "U$20") (pin "P$1") (pinfunction "P$1_P$1") (pintype "bidirectional"))
      (node (ref "U3") (pin "3") (pinfunction "C(3)_3") (pintype "input"))
    )
    (net (code "51") (name "Y_DIR") (class "Default")
      (node (ref "RYD1") (pin "1") (pinfunction "1_1") (pintype "passive"))
      (node (ref "U$26") (pin "P$5") (pinfunction "P$5_P$5") (pintype "bidirectional"))
    )
    (net (code "52") (name "Y_DIR_OUT") (class "Default")
      (node (ref "U$20") (pin "P$4") (pinfunction "P$4_P$4") (pintype "bidirectional"))
      (node (ref "U6") (pin "3") (pinfunction "C(3)_3") (pintype "input"))
    )
    (net (code "53") (name "Y_LS") (class "Default")
      (node (ref "U$25") (pin "1") (pinfunction "1_1") (pintype "passive"))
      (node (ref "U$26") (pin "P$4") (pinfunction "P$4_P$4") (pintype "bidirectional"))
      (node (ref "U$28") (pin "P$3") (pinfunction "P$3_P$3") (pintype "bidirectional"))
      (node (ref "U$28") (pin "P$4") (pinfunction "P$4_P$4") (pintype "bidirectional"))
      (node (ref "U$28") (pin "P$5") (pinfunction "P$5_P$5") (pintype "bidirectional"))
      (node (ref "U$28") (pin "P$6") (pinfunction "P$6_P$6") (pintype "bidirectional"))
    )
    (net (code "54") (name "Y_STEP") (class "Default")
      (node (ref "RYS1") (pin "1") (pinfunction "1_1") (pintype "passive"))
      (node (ref "U$26") (pin "P$13") (pinfunction "P$13_P$13") (pintype "bidirectional"))
    )
    (net (code "55") (name "Y_STEP_OUT") (class "Default")
      (node (ref "U$20") (pin "P$3") (pinfunction "P$3_P$3") (pintype "bidirectional"))
      (node (ref "U5") (pin "3") (pinfunction "C(3)_3") (pintype "input"))
    )
    (net (code "56") (name "Z_DIR") (class "Default")
      (node (ref "RZD1") (pin "1") (pinfunction "1_1") (pintype "passive"))
      (node (ref "U$26") (pin "P$1") (pinfunction "P$1_P$1") (pintype "bidirectional"))
    )
    (net (code "57") (name "Z_DIR_OUT") (class "Default")
      (node (ref "U$20") (pin "P$6") (pinfunction "P$6_P$6") (pintype "bidirectional"))
      (node (ref "U2") (pin "3") (pinfunction "C(3)_3") (pintype "input"))
    )
    (net (code "58") (name "Z_LS") (class "Default")
      (node (ref "U$26") (pin "P$6") (pinfunction "P$6_P$6") (pintype "bidirectional"))
      (node (ref "U$27") (pin "1") (pinfunction "1_1") (pintype "passive"))
      (node (ref "U$29") (pin "P$3") (pinfunction "P$3_P$3") (pintype "bidirectional"))
      (node (ref "U$29") (pin "P$4") (pinfunction "P$4_P$4") (pintype "bidirectional"))
      (node (ref "U$29") (pin "P$5") (pinfunction "P$5_P$5") (pintype "bidirectional"))
      (node (ref "U$29") (pin "P$6") (pinfunction "P$6_P$6") (pintype "bidirectional"))
    )
    (net (code "59") (name "Z_STEP") (class "Default")
      (node (ref "RZS1") (pin "1") (pinfunction "1_1") (pintype "passive"))
      (node (ref "U$26") (pin "P$9") (pinfunction "P$9_P$9") (pintype "bidirectional"))
    )
    (net (code "60") (name "Z_STEP_OUT") (class "Default")
      (node (ref "U$20") (pin "P$5") (pinfunction "P$5_P$5") (pintype "bidirectional"))
      (node (ref "U1") (pin "3") (pinfunction "C(3)_3") (pintype "input"))
    )
    (net (code "61") (name "unconnected-(J3--12V-Pad14)") (class "Default")
      (node (ref "J3") (pin "14") (pinfunction "-12V_14") (pintype "bidirectional"))
    )
    (net (code "62") (name "unconnected-(J3-12V-Pad10)") (class "Default")
      (node (ref "J3") (pin "10") (pinfunction "12V_10") (pintype "bidirectional"))
    )
    (net (code "63") (name "unconnected-(J3-12V-Pad11)") (class "Default")
      (node (ref "J3") (pin "11") (pinfunction "12V_11") (pintype "bidirectional"))
    )
    (net (code "64") (name "unconnected-(J3-NC-Pad20)") (class "Default")
      (node (ref "J3") (pin "20") (pinfunction "NC_20") (pintype "bidirectional"))
    )
  )
)
